# tinyJTAG-v10.net
KiCad netlist of a schematic drawn in EAGLE
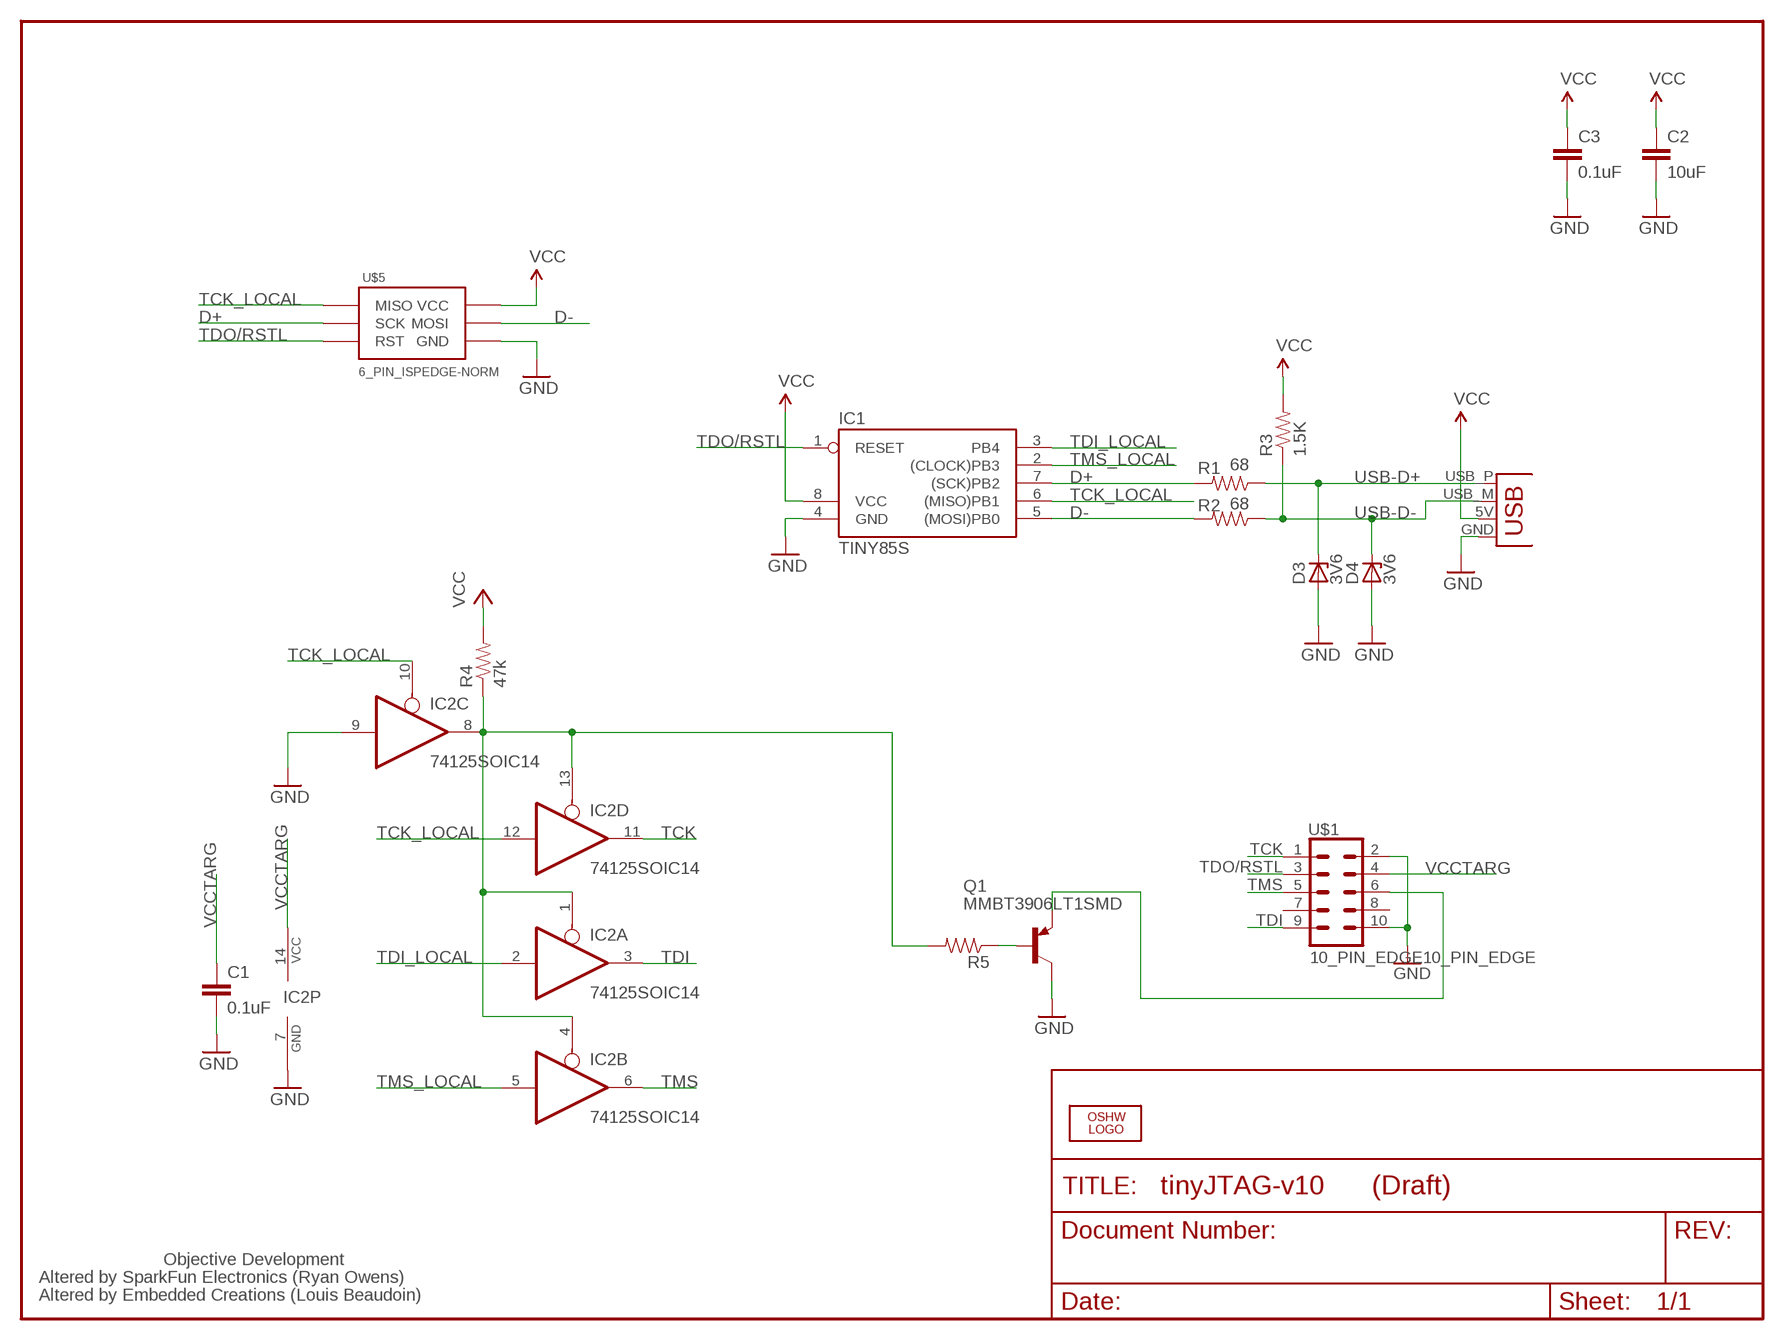
[diagram p0: schematic, sheet 1]

(export (version "E")
  (design (tool "Eeschema 10.0.6"))
  (components
    (comp (ref "C1")
      (value "0.1uF")
      (footprint "eagle-import:0603-CAP")
      (libsource (lib "eagle-import") (part "CAP0603-CAP"))
    )
    (comp (ref "C2")
      (value "10uF")
      (footprint "eagle-import:C0805")
      (libsource (lib "eagle-import") (part "C-EUC0805"))
    )
    (comp (ref "C3")
      (value "0.1uF")
      (footprint "eagle-import:0603-CAP")
      (libsource (lib "eagle-import") (part "CAP0603-CAP"))
    )
    (comp (ref "D3")
      (value "3V6")
      (footprint "eagle-import:DIODE_SOD323-W")
      (libsource (lib "eagle-import") (part "ZENER-DIODESOD323"))
    )
    (comp (ref "D4")
      (value "3V6")
      (footprint "eagle-import:DIODE_SOD323-W")
      (libsource (lib "eagle-import") (part "ZENER-DIODESOD323"))
    )
    (comp (ref "IC1")
      (value "TINY85S")
      (footprint "eagle-import:SOIC8")
      (libsource (lib "eagle-import") (part "TINY85S"))
    )
    (comp (ref "IC2")
      (value "74125SOIC14")
      (footprint "eagle-import:SO14")
      (libsource (lib "eagle-import") (part "74125SOIC14"))
    )
    (comp (ref "LOGO1")
      (value "OSHW_LOGO_FILLX0150-NT")
      (footprint "eagle-import:OSHW_FILLX150_NOTEXT")
      (libsource (lib "eagle-import") (part "OSHW_LOGO_FILLX0150-NT"))
    )
    (comp (ref "Q1")
      (value "MMBT3906LT1SMD")
      (footprint "eagle-import:SOT23-BEC")
      (libsource (lib "eagle-import") (part "MMBT3906SMDLT1"))
    )
    (comp (ref "R1")
      (value "68")
      (footprint "eagle-import:0603-RES")
      (libsource (lib "eagle-import") (part "RESISTOR0603-RES"))
    )
    (comp (ref "R2")
      (value "68")
      (footprint "eagle-import:0603-RES")
      (libsource (lib "eagle-import") (part "RESISTOR0603-RES"))
    )
    (comp (ref "R3")
      (value "1.5K")
      (footprint "eagle-import:0603-RES")
      (libsource (lib "eagle-import") (part "RESISTOR0603-RES"))
    )
    (comp (ref "R4")
      (value "47k")
      (footprint "eagle-import:0603-RES")
      (libsource (lib "eagle-import") (part "RESISTOR0603-RES"))
    )
    (comp (ref "R5")
      (value "RESISTOR0603-RES")
      (footprint "eagle-import:0603-RES")
      (libsource (lib "eagle-import") (part "RESISTOR0603-RES"))
    )
    (comp (ref "U$1")
      (value "10_PIN_EDGE10_PIN_EDGE")
      (footprint "eagle-import:10_PIN_EDGE")
      (libsource (lib "eagle-import") (part "10_PIN_EDGE10_PIN_EDGE"))
    )
    (comp (ref "U$5")
      (value "6_PIN_ISPEDGE-NORM")
      (footprint "eagle-import:6_PIN_EDGE")
      (libsource (lib "eagle-import") (part "6_PIN_ISPEDGE-NORM"))
    )
    (comp (ref "X1")
      (value "USBPCB")
      (footprint "eagle-import:USB-A-PCB")
      (libsource (lib "eagle-import") (part "USBPCB"))
    )
  )
  (nets
    (net (code "1") (name "/D+") (class "Default")
      (node (ref "IC1") (pin "7") (pinfunction "(SCK)PB2_7") (pintype "bidirectional"))
      (node (ref "R1") (pin "2") (pinfunction "2_2") (pintype "passive"))
      (node (ref "U$5") (pin "3") (pinfunction "SCK_3") (pintype "bidirectional"))
    )
    (net (code "2") (name "/D-") (class "Default")
      (node (ref "IC1") (pin "5") (pinfunction "(MOSI)PB0_5") (pintype "bidirectional"))
      (node (ref "R2") (pin "2") (pinfunction "2_2") (pintype "passive"))
      (node (ref "U$5") (pin "4") (pinfunction "MOSI_4") (pintype "bidirectional"))
    )
    (net (code "3") (name "/TCK") (class "Default")
      (node (ref "IC2") (pin "11") (pinfunction "O_11") (pintype "tri_state"))
      (node (ref "U$1") (pin "1") (pinfunction "1_1") (pintype "passive"))
    )
    (net (code "4") (name "/TCK_LOCAL") (class "Default")
      (node (ref "IC1") (pin "6") (pinfunction "(MISO)PB1_6") (pintype "bidirectional"))
      (node (ref "IC2") (pin "10") (pinfunction "OE_10") (pintype "input"))
      (node (ref "IC2") (pin "12") (pinfunction "I_12") (pintype "input"))
      (node (ref "U$5") (pin "1") (pinfunction "MISO_1") (pintype "bidirectional"))
    )
    (net (code "5") (name "/TDI") (class "Default")
      (node (ref "IC2") (pin "3") (pinfunction "O_3") (pintype "tri_state"))
      (node (ref "U$1") (pin "9") (pinfunction "9_9") (pintype "passive"))
    )
    (net (code "6") (name "/TDI_LOCAL") (class "Default")
      (node (ref "IC1") (pin "3") (pinfunction "PB4_3") (pintype "bidirectional"))
      (node (ref "IC2") (pin "2") (pinfunction "I_2") (pintype "input"))
    )
    (net (code "7") (name "/TDO{slash}RSTL") (class "Default")
      (node (ref "IC1") (pin "1") (pinfunction "RESET_1") (pintype "input"))
      (node (ref "U$1") (pin "3") (pinfunction "3_3") (pintype "passive"))
      (node (ref "U$5") (pin "5") (pinfunction "RST_5") (pintype "bidirectional"))
    )
    (net (code "8") (name "/TMS") (class "Default")
      (node (ref "IC2") (pin "6") (pinfunction "O_6") (pintype "tri_state"))
      (node (ref "U$1") (pin "5") (pinfunction "5_5") (pintype "passive"))
    )
    (net (code "9") (name "/TMS_LOCAL") (class "Default")
      (node (ref "IC1") (pin "2") (pinfunction "(CLOCK)PB3_2") (pintype "bidirectional"))
      (node (ref "IC2") (pin "5") (pinfunction "I_5") (pintype "input"))
    )
    (net (code "10") (name "/USB-D+") (class "Default")
      (node (ref "D3") (pin "C") (pinfunction "C_C") (pintype "passive"))
      (node (ref "R1") (pin "1") (pinfunction "1_1") (pintype "passive"))
      (node (ref "X1") (pin "USB_P") (pinfunction "D+_USB_P") (pintype "bidirectional"))
    )
    (net (code "11") (name "/USB-D-") (class "Default")
      (node (ref "D4") (pin "C") (pinfunction "C_C") (pintype "passive"))
      (node (ref "R2") (pin "1") (pinfunction "1_1") (pintype "passive"))
      (node (ref "R3") (pin "1") (pinfunction "1_1") (pintype "passive"))
      (node (ref "X1") (pin "USB_M") (pinfunction "D-_USB_M") (pintype "bidirectional"))
    )
    (net (code "12") (name "/VCCTARG") (class "Default")
      (node (ref "C1") (pin "1") (pinfunction "1_1") (pintype "passive"))
      (node (ref "IC2") (pin "14") (pinfunction "VCC_14") (pintype "power_in"))
      (node (ref "U$1") (pin "4") (pinfunction "4_4") (pintype "passive"))
    )
    (net (code "13") (name "GND") (class "Default")
      (node (ref "C1") (pin "2") (pinfunction "2_2") (pintype "passive"))
      (node (ref "C2") (pin "2") (pinfunction "2_2") (pintype "passive"))
      (node (ref "C3") (pin "2") (pinfunction "2_2") (pintype "passive"))
      (node (ref "D3") (pin "A") (pinfunction "A_A") (pintype "passive"))
      (node (ref "D4") (pin "A") (pinfunction "A_A") (pintype "passive"))
      (node (ref "IC1") (pin "4") (pinfunction "GND_4") (pintype "power_in"))
      (node (ref "IC2") (pin "7") (pinfunction "GND_7") (pintype "power_in"))
      (node (ref "IC2") (pin "9") (pinfunction "I_9") (pintype "input"))
      (node (ref "Q1") (pin "C") (pinfunction "C_C") (pintype "passive"))
      (node (ref "U$1") (pin "10") (pinfunction "10_10") (pintype "passive"))
      (node (ref "U$1") (pin "2") (pinfunction "2_2") (pintype "passive"))
      (node (ref "U$5") (pin "6") (pinfunction "GND_6") (pintype "power_in"))
      (node (ref "X1") (pin "GND") (pinfunction "GND_GND") (pintype "bidirectional"))
    )
    (net (code "14") (name "Net-(IC2A-OE)") (class "Default")
      (node (ref "IC2") (pin "1") (pinfunction "OE_1") (pintype "input"))
      (node (ref "IC2") (pin "13") (pinfunction "OE_13") (pintype "input"))
      (node (ref "IC2") (pin "4") (pinfunction "OE_4") (pintype "input"))
      (node (ref "IC2") (pin "8") (pinfunction "O_8") (pintype "tri_state"))
      (node (ref "R4") (pin "1") (pinfunction "1_1") (pintype "passive"))
      (node (ref "R5") (pin "2") (pinfunction "2_2") (pintype "passive"))
    )
    (net (code "15") (name "Net-(Q1-PadB)") (class "Default")
      (node (ref "Q1") (pin "B") (pinfunction "B_B") (pintype "passive"))
      (node (ref "R5") (pin "1") (pinfunction "1_1") (pintype "passive"))
    )
    (net (code "16") (name "Net-(Q1-PadE)") (class "Default")
      (node (ref "Q1") (pin "E") (pinfunction "E_E") (pintype "passive"))
      (node (ref "U$1") (pin "6") (pinfunction "6_6") (pintype "passive"))
    )
    (net (code "17") (name "VCC") (class "Default")
      (node (ref "C2") (pin "1") (pinfunction "1_1") (pintype "passive"))
      (node (ref "C3") (pin "1") (pinfunction "1_1") (pintype "passive"))
      (node (ref "IC1") (pin "8") (pinfunction "VCC_8") (pintype "power_in"))
      (node (ref "R3") (pin "2") (pinfunction "2_2") (pintype "passive"))
      (node (ref "R4") (pin "2") (pinfunction "2_2") (pintype "passive"))
      (node (ref "U$5") (pin "2") (pinfunction "VCC_2") (pintype "power_in"))
      (node (ref "X1") (pin "5V") (pinfunction "VBUS_5V") (pintype "bidirectional"))
    )
    (net (code "18") (name "unconnected-(U$1-Pad7)") (class "Default")
      (node (ref "U$1") (pin "7") (pinfunction "7_7") (pintype "passive"))
    )
    (net (code "19") (name "unconnected-(U$1-Pad8)") (class "Default")
      (node (ref "U$1") (pin "8") (pinfunction "8_8") (pintype "passive"))
    )
  )
)
